# ch32v003f4p6.net
KiCad netlist of a schematic drawn in Altium Designer
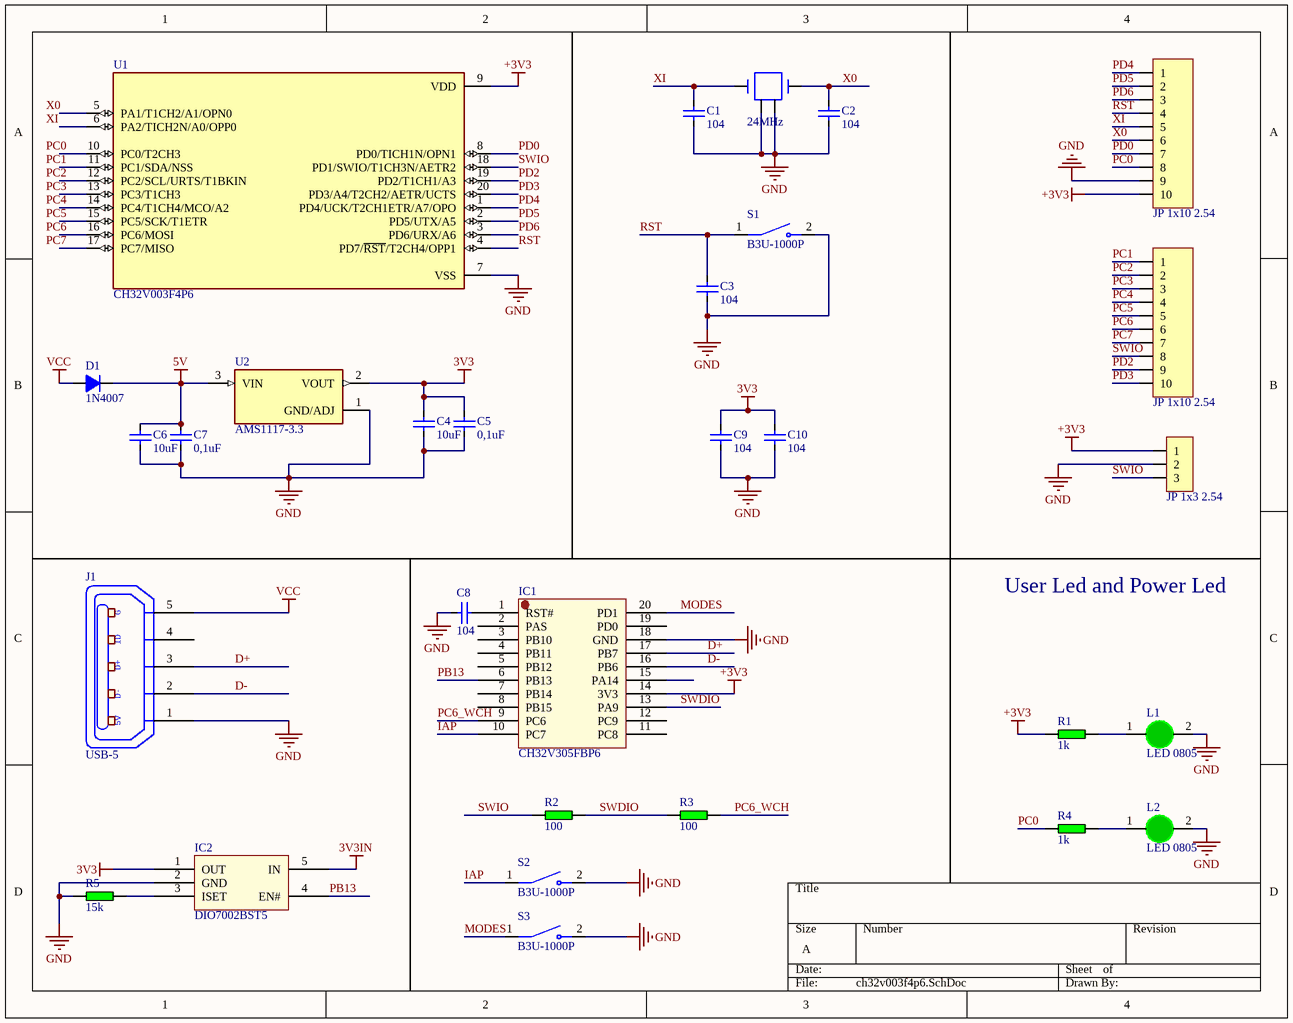
[diagram p0: ch32v003f4p6.SchDoc]

(export (version "E")
  (design (tool "Eeschema 10.0.6"))
  (components
    (comp (ref "C1")
      (value "104")
      (footprint "CAP_0603")
      (description "Capacitor")
      (fields (field (name "PUBLISHER") "Altium Limited"))
      (libsource (lib "My Library") (part "CapSMD"))
    )
    (comp (ref "C2")
      (value "104")
      (footprint "CAP_0603")
      (description "Capacitor")
      (fields (field (name "PUBLISHER") "Altium Limited"))
      (libsource (lib "My Library") (part "CapSMD"))
    )
    (comp (ref "C3")
      (value "104")
      (footprint "CAP_0603")
      (description "Capacitor")
      (fields (field (name "PUBLISHER") "Altium Limited"))
      (libsource (lib "My Library") (part "CapSMD"))
    )
    (comp (ref "C4")
      (value "10uF")
      (footprint "CAP_0603")
      (description "Capacitor")
      (fields (field (name "PUBLISHER") "Altium Limited"))
      (libsource (lib "My Library") (part "CapSMD"))
    )
    (comp (ref "C5")
      (value "0,1uF")
      (footprint "CAP_0603")
      (description "Capacitor")
      (fields (field (name "PUBLISHER") "Altium Limited"))
      (libsource (lib "My Library") (part "CapSMD"))
    )
    (comp (ref "C6")
      (value "10uF")
      (footprint "CAP_0603")
      (description "Capacitor")
      (fields (field (name "PUBLISHER") "Altium Limited"))
      (libsource (lib "My Library") (part "CapSMD"))
    )
    (comp (ref "C7")
      (value "0,1uF")
      (footprint "CAP_0603")
      (description "Capacitor")
      (fields (field (name "PUBLISHER") "Altium Limited"))
      (libsource (lib "My Library") (part "CapSMD"))
    )
    (comp (ref "C8")
      (value "104")
      (footprint "CAP_0603")
      (description "Capacitor")
      (fields (field (name "PUBLISHER") "Altium Limited"))
      (libsource (lib "My Library") (part "CapSMD"))
    )
    (comp (ref "C9")
      (value "104")
      (footprint "CAP_0603")
      (description "Capacitor")
      (fields (field (name "PUBLISHER") "Altium Limited"))
      (libsource (lib "My Library") (part "CapSMD"))
    )
    (comp (ref "C10")
      (value "104")
      (footprint "CAP_0603")
      (description "Capacitor")
      (fields (field (name "PUBLISHER") "Altium Limited"))
      (libsource (lib "My Library") (part "CapSMD"))
    )
    (comp (ref "D1")
      (value "1N4007")
      (footprint "DIO-214AC(SMA)")
      (description "Diode 1A")
      (libsource (lib "My Library 2") (part "D1A"))
    )
    (comp (ref "IC1")
      (value "CH32V305FBP6")
      (footprint "TSSOP-20")
      (libsource (lib "CH32V305FBP6") (part "CH32V305FBP6"))
    )
    (comp (ref "IC2")
      (value "DIO7002BST5")
      (footprint "SOT23-5")
      (libsource (lib "DIO7002BST5") (part "DIO7002BST5 SMD"))
    )
    (comp (ref "J1")
      (value "USB-5")
      (footprint "USB-M1")
      (fields
        (field (name "MANUFACTURER") "FCI")
        (field (name "MANUFACTURER PART NUMBER") "10118193-0001LF")
        (field (name ".CREATOR") "MM")
        (field (name ".CHECKED PCB") "RF")
        (field (name ".CHECKED SCH") "MM")
      )
      (libsource (lib "My Library") (part "USB-5"))
    )
    (comp (ref "JP1")
      (value "JP 1x10 2.54")
      (footprint "JP 1x10 DT")
      (description "Cắm")
      (libsource (lib "Altium_Lib_by_KhueNguyenCreator") (part "JP 1x10 2.54 Duc Thang"))
    )
    (comp (ref "JP2")
      (value "JP 1x10 2.54")
      (footprint "JP 1x10 DT")
      (description "Cắm")
      (libsource (lib "Altium_Lib_by_KhueNguyenCreator") (part "JP 1x10 2.54 Duc Thang"))
    )
    (comp (ref "JP3")
      (value "JP 1x3 2.54")
      (footprint "JP 1x3 DC")
      (description "Cắm")
      (libsource (lib "Altium_Lib_by_KhueNguyenCreator") (part "JP 1x3 2.54 Duc Cong"))
    )
    (comp (ref "L1")
      (value "LED 0805")
      (footprint "LED-0805-Green")
      (description "Dán")
      (libsource (lib "Altium_Lib_by_KhueNguyenCreator") (part "LED 0805 Xanh La"))
    )
    (comp (ref "L2")
      (value "LED 0805")
      (footprint "LED-0805-Green")
      (description "Dán")
      (libsource (lib "Altium_Lib_by_KhueNguyenCreator") (part "LED 0805 Xanh La"))
    )
    (comp (ref "R1")
      (value "1k")
      (footprint "RES-SMD-0603")
      (description "Resistor 1/4W")
      (libsource (lib "My Library 2") (part "RES"))
    )
    (comp (ref "R2")
      (value "100")
      (footprint "RES-SMD-0603")
      (description "Resistor 1/4W")
      (libsource (lib "My Library 2") (part "RES"))
    )
    (comp (ref "R3")
      (value "100")
      (footprint "RES-SMD-0603")
      (description "Resistor 1/4W")
      (libsource (lib "My Library 2") (part "RES"))
    )
    (comp (ref "R4")
      (value "1k")
      (footprint "RES-SMD-0603")
      (description "Resistor 1/4W")
      (libsource (lib "My Library 2") (part "RES"))
    )
    (comp (ref "R5")
      (value "15k")
      (footprint "RES-SMD-0603")
      (description "Resistor 1/4W")
      (libsource (lib "My Library 2") (part "RES"))
    )
    (comp (ref "S1")
      (value "B3U-1000P")
      (footprint "SW_B3U-1000P")
      (description "Switch Tactile N.O. SPST Round Button Gull Wing 0.05A 12VDC 1.5N SMD Embossed T/R")
      (libsource (lib "B3U-1000P") (part "B3U-1000P"))
    )
    (comp (ref "S2")
      (value "B3U-1000P")
      (footprint "SW_B3U-1000P")
      (description "Switch Tactile N.O. SPST Round Button Gull Wing 0.05A 12VDC 1.5N SMD Embossed T/R")
      (libsource (lib "B3U-1000P") (part "B3U-1000P"))
    )
    (comp (ref "S3")
      (value "B3U-1000P")
      (footprint "SW_B3U-1000P")
      (description "Switch Tactile N.O. SPST Round Button Gull Wing 0.05A 12VDC 1.5N SMD Embossed T/R")
      (libsource (lib "B3U-1000P") (part "B3U-1000P"))
    )
    (comp (ref "U1")
      (value "CH32V003F4P6")
      (footprint "SOP65P640X121-20N")
      (description "Industrial-grade general-purpose microcontroller")
      (fields (field (name "MF") "WCH"))
      (libsource (lib "CH32V003F4P6") (part "CH32V003F4P6"))
    )
    (comp (ref "U2")
      (value "AMS1117-3.3")
      (footprint "SOT229P700X180-4N")
      (description "Sot223/Pkg 1-Amp 3.3-Volt Low Drop Out Voltage Regulatator")
      (fields (field (name "MF") "Advanced Monolithic Systems"))
      (libsource (lib "AMS1117-3.3") (part "AMS1117-3.3"))
    )
    (comp (ref "Y1")
      (value "24MHz")
      (footprint "MinhTien_PcbLib:Crystal 4 pin SMD 50x32")
      (description "Crystal Oscillator")
      (fields (field (name "PUBLISHER") "Altium Limited"))
      (libsource (lib "MinhTien_SCHLib") (part "XTAL_4Pin SMD"))
    )
  )
  (nets
    (net (code "1") (name "+3V3") (class "Default")
      (node (ref "IC1") (pin "14") (pinfunction "3V3_14") (pintype "passive"))
      (node (ref "JP1") (pin "10") (pinfunction "10_10") (pintype "passive"))
      (node (ref "JP3") (pin "1") (pinfunction "1_1") (pintype "passive"))
      (node (ref "R1") (pin "2") (pinfunction "2_2") (pintype "passive"))
      (node (ref "U1") (pin "9") (pinfunction "VDD_9") (pintype "power_in"))
    )
    (net (code "2") (name "/D+") (class "Default")
      (node (ref "IC1") (pin "17") (pinfunction "PB7_17") (pintype "passive"))
      (node (ref "J1") (pin "3") (pinfunction "P3_3") (pintype "passive"))
    )
    (net (code "3") (name "/D-") (class "Default")
      (node (ref "IC1") (pin "16") (pinfunction "PB6_16") (pintype "passive"))
      (node (ref "J1") (pin "2") (pinfunction "P2_2") (pintype "passive"))
    )
    (net (code "4") (name "/IAP") (class "Default")
      (node (ref "IC1") (pin "10") (pinfunction "PC7_10") (pintype "passive"))
      (node (ref "S2") (pin "1") (pinfunction "1_1") (pintype "passive"))
    )
    (net (code "5") (name "/MODES") (class "Default")
      (node (ref "IC1") (pin "20") (pinfunction "PD1_20") (pintype "passive"))
      (node (ref "S3") (pin "1") (pinfunction "1_1") (pintype "passive"))
    )
    (net (code "6") (name "/PB13") (class "Default")
      (node (ref "IC1") (pin "6") (pinfunction "PB13_6") (pintype "passive"))
      (node (ref "IC2") (pin "4") (pinfunction "EN#_4") (pintype "passive"))
    )
    (net (code "7") (name "/PC0") (class "Default")
      (node (ref "JP1") (pin "8") (pinfunction "8_8") (pintype "passive"))
      (node (ref "R4") (pin "2") (pinfunction "2_2") (pintype "passive"))
    )
    (net (code "8") (name "/PC1") (class "Default")
      (node (ref "JP2") (pin "1") (pinfunction "1_1") (pintype "passive"))
    )
    (net (code "9") (name "/PC2") (class "Default")
      (node (ref "JP2") (pin "2") (pinfunction "2_2") (pintype "passive"))
    )
    (net (code "10") (name "/PC3") (class "Default")
      (node (ref "JP2") (pin "3") (pinfunction "3_3") (pintype "passive"))
    )
    (net (code "11") (name "/PC4") (class "Default")
      (node (ref "JP2") (pin "4") (pinfunction "4_4") (pintype "passive"))
    )
    (net (code "12") (name "/PC5") (class "Default")
      (node (ref "JP2") (pin "5") (pinfunction "5_5") (pintype "passive"))
    )
    (net (code "13") (name "/PC6") (class "Default")
      (node (ref "JP2") (pin "6") (pinfunction "6_6") (pintype "passive"))
    )
    (net (code "14") (name "/PC6_WCH") (class "Default")
      (node (ref "IC1") (pin "9") (pinfunction "PC6_9") (pintype "passive"))
      (node (ref "R3") (pin "1") (pinfunction "1_1") (pintype "passive"))
    )
    (net (code "15") (name "/PC7") (class "Default")
      (node (ref "JP2") (pin "7") (pinfunction "7_7") (pintype "passive"))
    )
    (net (code "16") (name "/PD0") (class "Default")
      (node (ref "JP1") (pin "7") (pinfunction "7_7") (pintype "passive"))
      (node (ref "U1") (pin "8") (pinfunction "PD0/TICH1N/OPN1_8") (pintype "bidirectional"))
    )
    (net (code "17") (name "/PD2") (class "Default")
      (node (ref "JP2") (pin "9") (pinfunction "9_9") (pintype "passive"))
      (node (ref "U1") (pin "19") (pinfunction "PD2/T1CH1/A3_19") (pintype "bidirectional"))
    )
    (net (code "18") (name "/PD3") (class "Default")
      (node (ref "JP2") (pin "10") (pinfunction "10_10") (pintype "passive"))
      (node (ref "U1") (pin "20") (pinfunction "PD3/A4/T2CH2/AETR/UCTS_20") (pintype "bidirectional"))
    )
    (net (code "19") (name "/PD4") (class "Default")
      (node (ref "JP1") (pin "1") (pinfunction "1_1") (pintype "passive"))
      (node (ref "U1") (pin "1") (pinfunction "PD4/UCK/T2CH1ETR/A7/OPO_1") (pintype "bidirectional"))
    )
    (net (code "20") (name "/PD5") (class "Default")
      (node (ref "JP1") (pin "2") (pinfunction "2_2") (pintype "passive"))
      (node (ref "U1") (pin "2") (pinfunction "PD5/UTX/A5_2") (pintype "bidirectional"))
    )
    (net (code "21") (name "/PD6") (class "Default")
      (node (ref "JP1") (pin "3") (pinfunction "3_3") (pintype "passive"))
      (node (ref "U1") (pin "3") (pinfunction "PD6/URX/A6_3") (pintype "bidirectional"))
    )
    (net (code "22") (name "/RST") (class "Default")
      (node (ref "C3") (pin "2") (pinfunction "2_2") (pintype "passive"))
      (node (ref "JP1") (pin "4") (pinfunction "4_4") (pintype "passive"))
      (node (ref "S1") (pin "1") (pinfunction "1_1") (pintype "passive"))
      (node (ref "U1") (pin "4") (pinfunction "PD7/~{RST}/T2CH4/OPP1_4") (pintype "bidirectional"))
    )
    (net (code "23") (name "/SWDIO") (class "Default")
      (node (ref "IC1") (pin "13") (pinfunction "PA9_13") (pintype "passive"))
      (node (ref "R2") (pin "1") (pinfunction "1_1") (pintype "passive"))
      (node (ref "R3") (pin "2") (pinfunction "2_2") (pintype "passive"))
    )
    (net (code "24") (name "/SWIO") (class "Default")
      (node (ref "JP2") (pin "8") (pinfunction "8_8") (pintype "passive"))
      (node (ref "JP3") (pin "3") (pinfunction "3_3") (pintype "passive"))
      (node (ref "R2") (pin "2") (pinfunction "2_2") (pintype "passive"))
      (node (ref "U1") (pin "18") (pinfunction "PD1/SWIO/T1CH3N/AETR2_18") (pintype "bidirectional"))
    )
    (net (code "25") (name "/X0") (class "Default")
      (node (ref "C2") (pin "2") (pinfunction "2_2") (pintype "passive"))
      (node (ref "JP1") (pin "6") (pinfunction "6_6") (pintype "passive"))
      (node (ref "Y1") (pin "3") (pinfunction "OSC2_3") (pintype "passive"))
    )
    (net (code "26") (name "/XI") (class "Default")
      (node (ref "C1") (pin "2") (pinfunction "2_2") (pintype "passive"))
      (node (ref "JP1") (pin "5") (pinfunction "5_5") (pintype "passive"))
      (node (ref "Y1") (pin "1") (pinfunction "OSC1_1") (pintype "passive"))
    )
    (net (code "27") (name "3V3") (class "Default")
      (node (ref "C10") (pin "2") (pinfunction "2_2") (pintype "passive"))
      (node (ref "C4") (pin "2") (pinfunction "2_2") (pintype "passive"))
      (node (ref "C5") (pin "2") (pinfunction "2_2") (pintype "passive"))
      (node (ref "C9") (pin "2") (pinfunction "2_2") (pintype "passive"))
      (node (ref "IC2") (pin "1") (pinfunction "OUT_1") (pintype "passive"))
      (node (ref "U2") (pin "2") (pinfunction "VOUT_2") (pintype "output"))
    )
    (net (code "28") (name "3V3IN") (class "Default")
      (node (ref "IC2") (pin "5") (pinfunction "IN_5") (pintype "passive"))
    )
    (net (code "29") (name "5V") (class "Default")
      (node (ref "C6") (pin "2") (pinfunction "2_2") (pintype "passive"))
      (node (ref "C7") (pin "2") (pinfunction "2_2") (pintype "passive"))
      (node (ref "D1") (pin "2") (pinfunction "K_2") (pintype "passive"))
      (node (ref "U2") (pin "3") (pinfunction "VIN_3") (pintype "input"))
    )
    (net (code "30") (name "GND") (class "Default")
      (node (ref "C1") (pin "1") (pinfunction "1_1") (pintype "passive"))
      (node (ref "C10") (pin "1") (pinfunction "1_1") (pintype "passive"))
      (node (ref "C2") (pin "1") (pinfunction "1_1") (pintype "passive"))
      (node (ref "C3") (pin "1") (pinfunction "1_1") (pintype "passive"))
      (node (ref "C4") (pin "1") (pinfunction "1_1") (pintype "passive"))
      (node (ref "C5") (pin "1") (pinfunction "1_1") (pintype "passive"))
      (node (ref "C6") (pin "1") (pinfunction "1_1") (pintype "passive"))
      (node (ref "C7") (pin "1") (pinfunction "1_1") (pintype "passive"))
      (node (ref "C8") (pin "1") (pinfunction "1_1") (pintype "passive"))
      (node (ref "C9") (pin "1") (pinfunction "1_1") (pintype "passive"))
      (node (ref "IC1") (pin "18") (pinfunction "GND_18") (pintype "passive"))
      (node (ref "IC2") (pin "2") (pinfunction "GND_2") (pintype "passive"))
      (node (ref "J1") (pin "1") (pinfunction "P1_1") (pintype "passive"))
      (node (ref "JP1") (pin "9") (pinfunction "9_9") (pintype "passive"))
      (node (ref "JP3") (pin "2") (pinfunction "2_2") (pintype "passive"))
      (node (ref "L1") (pin "2") (pinfunction "K_2") (pintype "passive"))
      (node (ref "L2") (pin "2") (pinfunction "K_2") (pintype "passive"))
      (node (ref "R5") (pin "2") (pinfunction "2_2") (pintype "passive"))
      (node (ref "S1") (pin "2") (pinfunction "2_2") (pintype "passive"))
      (node (ref "S2") (pin "2") (pinfunction "2_2") (pintype "passive"))
      (node (ref "S3") (pin "2") (pinfunction "2_2") (pintype "passive"))
      (node (ref "U1") (pin "7") (pinfunction "VSS_7") (pintype "power_in"))
      (node (ref "U2") (pin "1") (pinfunction "GND/ADJ_1") (pintype "power_in"))
      (node (ref "Y1") (pin "2") (pinfunction "GND_2") (pintype "passive"))
      (node (ref "Y1") (pin "4") (pinfunction "GND_4") (pintype "passive"))
    )
    (net (code "31") (name "Net-(IC1-RST#)") (class "Default")
      (node (ref "C8") (pin "2") (pinfunction "2_2") (pintype "passive"))
      (node (ref "IC1") (pin "1") (pinfunction "RST#_1") (pintype "passive"))
    )
    (net (code "32") (name "Net-(IC2-ISET)") (class "Default")
      (node (ref "IC2") (pin "3") (pinfunction "ISET_3") (pintype "passive"))
      (node (ref "R5") (pin "1") (pinfunction "1_1") (pintype "passive"))
    )
    (net (code "33") (name "Net-(L1-A)") (class "Default")
      (node (ref "L1") (pin "1") (pinfunction "A_1") (pintype "passive"))
      (node (ref "R1") (pin "1") (pinfunction "1_1") (pintype "passive"))
    )
    (net (code "34") (name "Net-(L2-A)") (class "Default")
      (node (ref "L2") (pin "1") (pinfunction "A_1") (pintype "passive"))
      (node (ref "R4") (pin "1") (pinfunction "1_1") (pintype "passive"))
    )
    (net (code "35") (name "VCC") (class "Default")
      (node (ref "D1") (pin "1") (pinfunction "A_1") (pintype "passive"))
      (node (ref "J1") (pin "5") (pinfunction "P5_5") (pintype "passive"))
    )
    (net (code "36") (name "unconnected-(IC1-PA14-Pad15)") (class "Default")
      (node (ref "IC1") (pin "15") (pinfunction "PA14_15") (pintype "passive"))
    )
    (net (code "37") (name "unconnected-(IC1-PAS-Pad2)") (class "Default")
      (node (ref "IC1") (pin "2") (pinfunction "PAS_2") (pintype "passive"))
    )
    (net (code "38") (name "unconnected-(IC1-PB10-Pad3)") (class "Default")
      (node (ref "IC1") (pin "3") (pinfunction "PB10_3") (pintype "passive"))
    )
    (net (code "39") (name "unconnected-(IC1-PB11-Pad4)") (class "Default")
      (node (ref "IC1") (pin "4") (pinfunction "PB11_4") (pintype "passive"))
    )
    (net (code "40") (name "unconnected-(IC1-PB12-Pad5)") (class "Default")
      (node (ref "IC1") (pin "5") (pinfunction "PB12_5") (pintype "passive"))
    )
    (net (code "41") (name "unconnected-(IC1-PB14-Pad7)") (class "Default")
      (node (ref "IC1") (pin "7") (pinfunction "PB14_7") (pintype "passive"))
    )
    (net (code "42") (name "unconnected-(IC1-PB15-Pad8)") (class "Default")
      (node (ref "IC1") (pin "8") (pinfunction "PB15_8") (pintype "passive"))
    )
    (net (code "43") (name "unconnected-(IC1-PC8-Pad11)") (class "Default")
      (node (ref "IC1") (pin "11") (pinfunction "PC8_11") (pintype "passive"))
    )
    (net (code "44") (name "unconnected-(IC1-PC9-Pad12)") (class "Default")
      (node (ref "IC1") (pin "12") (pinfunction "PC9_12") (pintype "passive"))
    )
    (net (code "45") (name "unconnected-(IC1-PD0-Pad19)") (class "Default")
      (node (ref "IC1") (pin "19") (pinfunction "PD0_19") (pintype "passive"))
    )
    (net (code "46") (name "unconnected-(J1-P4-Pad4)") (class "Default")
      (node (ref "J1") (pin "4") (pinfunction "P4_4") (pintype "passive"))
    )
    (net (code "47") (name "unconnected-(U1-PA1{slash}T1CH2{slash}A1{slash}OPN0-Pad5)") (class "Default")
      (node (ref "U1") (pin "5") (pinfunction "PA1/T1CH2/A1/OPN0_5") (pintype "bidirectional"))
    )
    (net (code "48") (name "unconnected-(U1-PA2{slash}TICH2N{slash}A0{slash}OPP0-Pad6)") (class "Default")
      (node (ref "U1") (pin "6") (pinfunction "PA2/TICH2N/A0/OPP0_6") (pintype "bidirectional"))
    )
    (net (code "49") (name "unconnected-(U1-PC0{slash}T2CH3-Pad10)") (class "Default")
      (node (ref "U1") (pin "10") (pinfunction "PC0/T2CH3_10") (pintype "bidirectional"))
    )
    (net (code "50") (name "unconnected-(U1-PC1{slash}SDA{slash}NSS-Pad11)") (class "Default")
      (node (ref "U1") (pin "11") (pinfunction "PC1/SDA/NSS_11") (pintype "bidirectional"))
    )
    (net (code "51") (name "unconnected-(U1-PC2{slash}SCL{slash}URTS{slash}T1BKIN-Pad12)") (class "Default")
      (node (ref "U1") (pin "12") (pinfunction "PC2/SCL/URTS/T1BKIN_12") (pintype "bidirectional"))
    )
    (net (code "52") (name "unconnected-(U1-PC3{slash}T1CH3-Pad13)") (class "Default")
      (node (ref "U1") (pin "13") (pinfunction "PC3/T1CH3_13") (pintype "bidirectional"))
    )
    (net (code "53") (name "unconnected-(U1-PC4{slash}T1CH4{slash}MCO{slash}A2-Pad14)") (class "Default")
      (node (ref "U1") (pin "14") (pinfunction "PC4/T1CH4/MCO/A2_14") (pintype "bidirectional"))
    )
    (net (code "54") (name "unconnected-(U1-PC5{slash}SCK{slash}T1ETR-Pad15)") (class "Default")
      (node (ref "U1") (pin "15") (pinfunction "PC5/SCK/T1ETR_15") (pintype "bidirectional"))
    )
    (net (code "55") (name "unconnected-(U1-PC6{slash}MOSI-Pad16)") (class "Default")
      (node (ref "U1") (pin "16") (pinfunction "PC6/MOSI_16") (pintype "bidirectional"))
    )
    (net (code "56") (name "unconnected-(U1-PC7{slash}MISO-Pad17)") (class "Default")
      (node (ref "U1") (pin "17") (pinfunction "PC7/MISO_17") (pintype "bidirectional"))
    )
  )
)
